# BMS_CellCircuit.net
KiCad netlist of a schematic drawn in Altium Designer
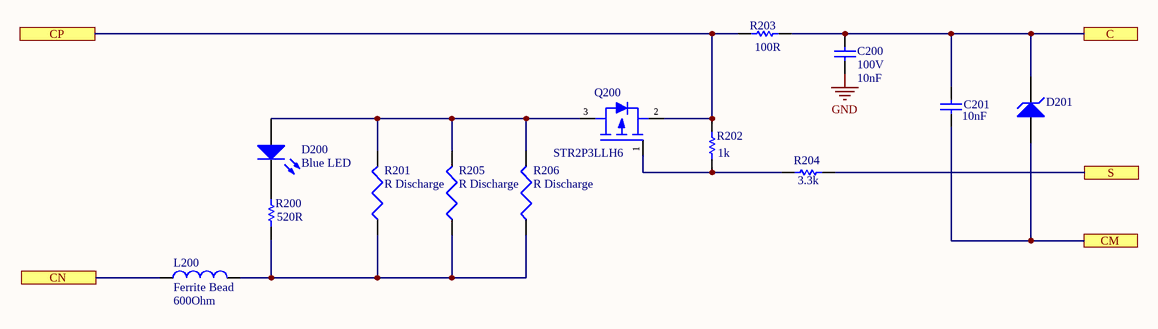
[diagram p0: BMS_CellCircuit.SchDoc]

(export (version "E")
  (design (tool "Eeschema 10.0.6"))
  (components
    (comp (ref "C200")
      (value "100V")
      (footprint "CAPC2012X14N")
      (description "Capacitor")
      (fields (field (name "ALTIUM_VALUE") "10nF") (field (name "PUBLISHER") "Altium Limited"))
      (libsource (lib "Miscellaneous Devices") (part "Cap"))
    )
    (comp (ref "C201")
      (value "10nF")
      (footprint "CAPC2012X14N")
      (description "Capacitor")
      (fields (field (name "Comment") "C0805") (field (name "PUBLISHER") "Altium Limited"))
      (libsource (lib "Miscellaneous Devices") (part "Cap"))
    )
    (comp (ref "D200")
      (value "Blue LED")
      (footprint "SMD Blue LED")
      (description "Typical INFRARED GaAs LED")
      (fields (field (name "PUBLISHER") "Altium Limited"))
      (libsource (lib "Miscellaneous Devices") (part "LED0"))
    )
    (comp (ref "D201")
      (value "D Zener 6.8V")
      (footprint "SODFL250X110-2N")
      (description "Zener Diodes PDZ6.8B/SOD2/REEL 13\" Q1/T1 *S")
      (fields (field (name "PUBLISHER") "Altium Limited"))
      (libsource (lib "Miscellaneous Devices") (part "D Zener"))
    )
    (comp (ref "L200")
      (value "Ferrite Bead")
      (footprint "INDC3216X13N")
      (description "Inductor")
      (fields (field (name "ALTIUM_VALUE") "600Ohm") (field (name "PUBLISHER") "Altium Limited"))
      (libsource (lib "Miscellaneous Devices") (part "Inductor"))
    )
    (comp (ref "Q200")
      (value "STR2P3LLH6")
      (footprint "SOT95P280X110-3N")
      (description "P-channel -30 V, 48 mΩ typICAL, -2 A STripFET™ H6 Power MOSFET in a SOT-23 package.")
      (libsource (lib "STR2P3LLH6") (part "STR2P3LLH6"))
    )
    (comp (ref "R200")
      (value "520R")
      (footprint "RESC2012X07N")
      (description "Resistor")
      (fields (field (name "Comment") "R0805") (field (name "PUBLISHER") "Altium Limited"))
      (libsource (lib "Miscellaneous Devices") (part "Res1"))
    )
    (comp (ref "R201")
      (value "R Discharge")
      (footprint "RESC1632X06N")
      (description "0612 Discharge Resistance - WK73R2BTTD42R2F")
      (libsource (lib "R-Discharge") (part "R Discharge"))
    )
    (comp (ref "R202")
      (value "1k")
      (footprint "RESC2012X07N")
      (description "Resistor")
      (fields (field (name "Comment") "R0805") (field (name "PUBLISHER") "Altium Limited"))
      (libsource (lib "Miscellaneous Devices") (part "Res1"))
    )
    (comp (ref "R203")
      (value "100R")
      (footprint "RESC2012X07N")
      (description "Resistor")
      (fields (field (name "Comment") "R0805") (field (name "PUBLISHER") "Altium Limited"))
      (libsource (lib "Miscellaneous Devices") (part "Res1"))
    )
    (comp (ref "R204")
      (value "3.3k")
      (footprint "RESC2012X07N")
      (description "Resistor")
      (fields (field (name "Comment") "R0805") (field (name "PUBLISHER") "Altium Limited"))
      (libsource (lib "Miscellaneous Devices") (part "Res1"))
    )
    (comp (ref "R205")
      (value "R Discharge")
      (footprint "RESC1632X06N")
      (description "0612 Discharge Resistance - WK73R2BTTD42R2F")
      (libsource (lib "R-Discharge") (part "R Discharge"))
    )
    (comp (ref "R206")
      (value "R Discharge")
      (footprint "RESC1632X06N")
      (description "0612 Discharge Resistance - WK73R2BTTD42R2F")
      (libsource (lib "R-Discharge") (part "R Discharge"))
    )
  )
  (nets
    (net (code "1") (name "/C") (class "Default")
      (node (ref "C200") (pin "1") (pinfunction "1_1") (pintype "passive"))
      (node (ref "C201") (pin "1") (pinfunction "1_1") (pintype "passive"))
      (node (ref "D201") (pin "2") (pinfunction "K_2") (pintype "passive"))
      (node (ref "R203") (pin "1") (pinfunction "1_1") (pintype "passive"))
    )
    (net (code "2") (name "/CM") (class "Default")
      (node (ref "C201") (pin "2") (pinfunction "2_2") (pintype "passive"))
      (node (ref "D201") (pin "1") (pinfunction "A_1") (pintype "passive"))
    )
    (net (code "3") (name "/CN") (class "Default")
      (node (ref "L200") (pin "1") (pinfunction "1_1") (pintype "passive"))
    )
    (net (code "4") (name "/CP") (class "Default")
      (node (ref "Q200") (pin "2") (pinfunction "2_2") (pintype "passive"))
      (node (ref "R202") (pin "2") (pinfunction "2_2") (pintype "passive"))
      (node (ref "R203") (pin "2") (pinfunction "2_2") (pintype "passive"))
    )
    (net (code "5") (name "/S") (class "Default")
      (node (ref "R204") (pin "1") (pinfunction "1_1") (pintype "passive"))
    )
    (net (code "6") (name "GND") (class "Default")
      (node (ref "C200") (pin "2") (pinfunction "2_2") (pintype "passive"))
    )
    (net (code "7") (name "Net-(D200-A)") (class "Default")
      (node (ref "D200") (pin "1") (pinfunction "A_1") (pintype "passive"))
      (node (ref "Q200") (pin "3") (pinfunction "3_3") (pintype "passive"))
      (node (ref "R201") (pin "2") (pinfunction "2_2") (pintype "passive"))
      (node (ref "R205") (pin "2") (pinfunction "2_2") (pintype "passive"))
      (node (ref "R206") (pin "2") (pinfunction "2_2") (pintype "passive"))
    )
    (net (code "8") (name "Net-(D200-K)") (class "Default")
      (node (ref "D200") (pin "2") (pinfunction "K_2") (pintype "passive"))
      (node (ref "R200") (pin "2") (pinfunction "2_2") (pintype "passive"))
    )
    (net (code "9") (name "Net-(L200-Pad2)") (class "Default")
      (node (ref "L200") (pin "2") (pinfunction "2_2") (pintype "passive"))
      (node (ref "R200") (pin "1") (pinfunction "1_1") (pintype "passive"))
      (node (ref "R201") (pin "1") (pinfunction "1_1") (pintype "passive"))
      (node (ref "R205") (pin "1") (pinfunction "1_1") (pintype "passive"))
      (node (ref "R206") (pin "1") (pinfunction "1_1") (pintype "passive"))
    )
    (net (code "10") (name "Net-(Q200-Pad1)") (class "Default")
      (node (ref "Q200") (pin "1") (pinfunction "1_1") (pintype "passive"))
      (node (ref "R202") (pin "1") (pinfunction "1_1") (pintype "passive"))
      (node (ref "R204") (pin "2") (pinfunction "2_2") (pintype "passive"))
    )
  )
)
